# Main.net
KiCad netlist of a schematic drawn in EAGLE
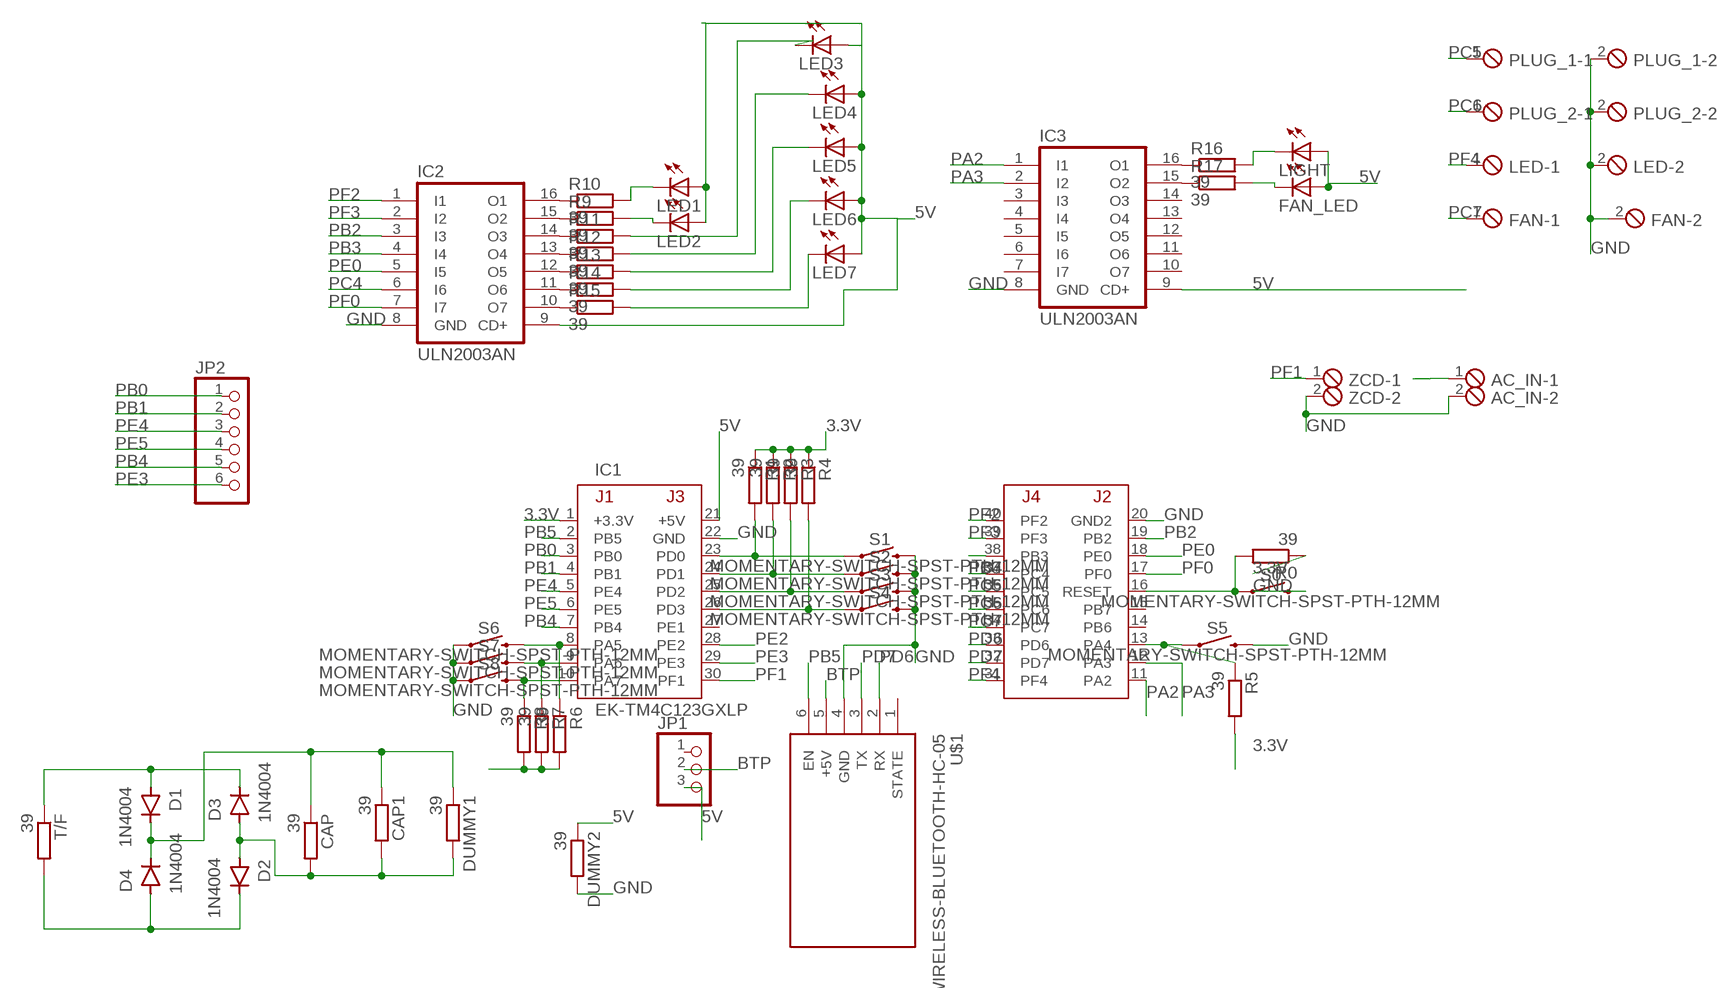
[diagram p0: schematic, sheet 1]

(export (version "E")
  (design (tool "Eeschema 10.0.6"))
  (components
    (comp (ref "AC_IN")
      (value "MPT2")
      (footprint "eagle-import:2POL254")
      (libsource (lib "eagle-import") (part "MPT2"))
    )
    (comp (ref "CAP")
      (value "39")
      (footprint "eagle-import:0204_7")
      (libsource (lib "eagle-import") (part "R0204/7"))
    )
    (comp (ref "CAP1")
      (value "39")
      (footprint "eagle-import:0204_7")
      (libsource (lib "eagle-import") (part "R0204/7"))
    )
    (comp (ref "D1")
      (value "1N4004")
      (footprint "eagle-import:DO-41")
      (fields
        (field (name "DIGIKEY_PART_NUMBER") "1N4004MSCT-ND")
        (field (name "MANUFACTURER") "Micro Commercial Co")
        (field (name "CREATED_BY") "PCBLayout.com")
      )
      (libsource (lib "eagle-import") (part "1N4004"))
    )
    (comp (ref "D2")
      (value "1N4004")
      (footprint "eagle-import:DO-41")
      (fields
        (field (name "DIGIKEY_PART_NUMBER") "1N4004MSCT-ND")
        (field (name "MANUFACTURER") "Micro Commercial Co")
        (field (name "CREATED_BY") "PCBLayout.com")
      )
      (libsource (lib "eagle-import") (part "1N4004"))
    )
    (comp (ref "D3")
      (value "1N4004")
      (footprint "eagle-import:DO-41")
      (fields
        (field (name "DIGIKEY_PART_NUMBER") "1N4004MSCT-ND")
        (field (name "MANUFACTURER") "Micro Commercial Co")
        (field (name "CREATED_BY") "PCBLayout.com")
      )
      (libsource (lib "eagle-import") (part "1N4004"))
    )
    (comp (ref "D4")
      (value "1N4004")
      (footprint "eagle-import:DO-41")
      (fields
        (field (name "DIGIKEY_PART_NUMBER") "1N4004MSCT-ND")
        (field (name "MANUFACTURER") "Micro Commercial Co")
        (field (name "CREATED_BY") "PCBLayout.com")
      )
      (libsource (lib "eagle-import") (part "1N4004"))
    )
    (comp (ref "DUMMY1")
      (value "39")
      (footprint "eagle-import:0204_7")
      (libsource (lib "eagle-import") (part "R0204/7"))
    )
    (comp (ref "DUMMY2")
      (value "39")
      (footprint "eagle-import:0204_7")
      (libsource (lib "eagle-import") (part "R0204/7"))
    )
    (comp (ref "FAN")
      (value "MPT2")
      (footprint "eagle-import:2POL254")
      (libsource (lib "eagle-import") (part "MPT2"))
    )
    (comp (ref "FAN_LED")
      (value "LED3MM")
      (footprint "eagle-import:LED3MM")
      (libsource (lib "eagle-import") (part "LED3MM"))
    )
    (comp (ref "IC1")
      (value "EK-TM4C123GXLP")
      (footprint "eagle-import:TM4C123LAUNCHPAD")
      (fields (field (name "MF") "Texas Instruments") (field (name "MP") "EK-TM4C123GXL"))
      (libsource (lib "eagle-import") (part "EK-TM4C123GXLP"))
    )
    (comp (ref "IC2")
      (value "ULN2003AN")
      (footprint "eagle-import:DIL16")
      (libsource (lib "eagle-import") (part "ULN2003AN"))
    )
    (comp (ref "IC3")
      (value "ULN2003AN")
      (footprint "eagle-import:DIL16")
      (libsource (lib "eagle-import") (part "ULN2003AN"))
    )
    (comp (ref "JP1")
      (value "PINHD-1X3CB")
      (footprint "eagle-import:1X03-CLEANBIG")
      (libsource (lib "eagle-import") (part "PINHD-1X3CB"))
    )
    (comp (ref "JP2")
      (value "PINHD-1X6")
      (footprint "eagle-import:1X06")
      (libsource (lib "eagle-import") (part "PINHD-1X6"))
    )
    (comp (ref "LED")
      (value "MPT2")
      (footprint "eagle-import:2POL254")
      (libsource (lib "eagle-import") (part "MPT2"))
    )
    (comp (ref "LED1")
      (value "LED3MM")
      (footprint "eagle-import:LED3MM")
      (libsource (lib "eagle-import") (part "LED3MM"))
    )
    (comp (ref "LED2")
      (value "LED3MM")
      (footprint "eagle-import:LED3MM")
      (libsource (lib "eagle-import") (part "LED3MM"))
    )
    (comp (ref "LED3")
      (value "LED3MM")
      (footprint "eagle-import:LED3MM")
      (libsource (lib "eagle-import") (part "LED3MM"))
    )
    (comp (ref "LED4")
      (value "LED3MM")
      (footprint "eagle-import:LED3MM")
      (libsource (lib "eagle-import") (part "LED3MM"))
    )
    (comp (ref "LED5")
      (value "LED3MM")
      (footprint "eagle-import:LED3MM")
      (libsource (lib "eagle-import") (part "LED3MM"))
    )
    (comp (ref "LED6")
      (value "LED3MM")
      (footprint "eagle-import:LED3MM")
      (libsource (lib "eagle-import") (part "LED3MM"))
    )
    (comp (ref "LED7")
      (value "LED3MM")
      (footprint "eagle-import:LED3MM")
      (libsource (lib "eagle-import") (part "LED3MM"))
    )
    (comp (ref "LIGHT")
      (value "LED3MM")
      (footprint "eagle-import:LED3MM")
      (libsource (lib "eagle-import") (part "LED3MM"))
    )
    (comp (ref "PLUG_1")
      (value "MPT2")
      (footprint "eagle-import:2POL254")
      (libsource (lib "eagle-import") (part "MPT2"))
    )
    (comp (ref "PLUG_2")
      (value "MPT2")
      (footprint "eagle-import:2POL254")
      (libsource (lib "eagle-import") (part "MPT2"))
    )
    (comp (ref "R0")
      (value "39")
      (footprint "eagle-import:0204_7")
      (libsource (lib "eagle-import") (part "R0204/7"))
    )
    (comp (ref "R1")
      (value "39")
      (footprint "eagle-import:0204_7")
      (libsource (lib "eagle-import") (part "R0204/7"))
    )
    (comp (ref "R2")
      (value "39")
      (footprint "eagle-import:0204_7")
      (libsource (lib "eagle-import") (part "R0204/7"))
    )
    (comp (ref "R3")
      (value "39")
      (footprint "eagle-import:0204_7")
      (libsource (lib "eagle-import") (part "R0204/7"))
    )
    (comp (ref "R4")
      (value "39")
      (footprint "eagle-import:0204_7")
      (libsource (lib "eagle-import") (part "R0204/7"))
    )
    (comp (ref "R5")
      (value "39")
      (footprint "eagle-import:0204_7")
      (libsource (lib "eagle-import") (part "R0204/7"))
    )
    (comp (ref "R6")
      (value "39")
      (footprint "eagle-import:0204_7")
      (libsource (lib "eagle-import") (part "R0204/7"))
    )
    (comp (ref "R7")
      (value "39")
      (footprint "eagle-import:0204_7")
      (libsource (lib "eagle-import") (part "R0204/7"))
    )
    (comp (ref "R8")
      (value "39")
      (footprint "eagle-import:0204_7")
      (libsource (lib "eagle-import") (part "R0204/7"))
    )
    (comp (ref "R9")
      (value "39")
      (footprint "eagle-import:0204_7")
      (libsource (lib "eagle-import") (part "R0204/7"))
    )
    (comp (ref "R10")
      (value "39")
      (footprint "eagle-import:0204_7")
      (libsource (lib "eagle-import") (part "R0204/7"))
    )
    (comp (ref "R11")
      (value "39")
      (footprint "eagle-import:0204_7")
      (libsource (lib "eagle-import") (part "R0204/7"))
    )
    (comp (ref "R12")
      (value "39")
      (footprint "eagle-import:0204_7")
      (libsource (lib "eagle-import") (part "R0204/7"))
    )
    (comp (ref "R13")
      (value "39")
      (footprint "eagle-import:0204_7")
      (libsource (lib "eagle-import") (part "R0204/7"))
    )
    (comp (ref "R14")
      (value "39")
      (footprint "eagle-import:0204_7")
      (libsource (lib "eagle-import") (part "R0204/7"))
    )
    (comp (ref "R15")
      (value "39")
      (footprint "eagle-import:0204_7")
      (libsource (lib "eagle-import") (part "R0204/7"))
    )
    (comp (ref "R16")
      (value "39")
      (footprint "eagle-import:0204_7")
      (libsource (lib "eagle-import") (part "R0204/7"))
    )
    (comp (ref "R17")
      (value "39")
      (footprint "eagle-import:0204_7")
      (libsource (lib "eagle-import") (part "R0204/7"))
    )
    (comp (ref "S0")
      (value "MOMENTARY-SWITCH-SPST-PTH-12MM")
      (footprint "eagle-import:TACTILE_SWITCH_PTH_12MM")
      (libsource (lib "eagle-import") (part "MOMENTARY-SWITCH-SPST-PTH-12MM"))
    )
    (comp (ref "S1")
      (value "MOMENTARY-SWITCH-SPST-PTH-12MM")
      (footprint "eagle-import:TACTILE_SWITCH_PTH_12MM")
      (libsource (lib "eagle-import") (part "MOMENTARY-SWITCH-SPST-PTH-12MM"))
    )
    (comp (ref "S2")
      (value "MOMENTARY-SWITCH-SPST-PTH-12MM")
      (footprint "eagle-import:TACTILE_SWITCH_PTH_12MM")
      (libsource (lib "eagle-import") (part "MOMENTARY-SWITCH-SPST-PTH-12MM"))
    )
    (comp (ref "S3")
      (value "MOMENTARY-SWITCH-SPST-PTH-12MM")
      (footprint "eagle-import:TACTILE_SWITCH_PTH_12MM")
      (libsource (lib "eagle-import") (part "MOMENTARY-SWITCH-SPST-PTH-12MM"))
    )
    (comp (ref "S4")
      (value "MOMENTARY-SWITCH-SPST-PTH-12MM")
      (footprint "eagle-import:TACTILE_SWITCH_PTH_12MM")
      (libsource (lib "eagle-import") (part "MOMENTARY-SWITCH-SPST-PTH-12MM"))
    )
    (comp (ref "S5")
      (value "MOMENTARY-SWITCH-SPST-PTH-12MM")
      (footprint "eagle-import:TACTILE_SWITCH_PTH_12MM")
      (libsource (lib "eagle-import") (part "MOMENTARY-SWITCH-SPST-PTH-12MM"))
    )
    (comp (ref "S6")
      (value "MOMENTARY-SWITCH-SPST-PTH-12MM")
      (footprint "eagle-import:TACTILE_SWITCH_PTH_12MM")
      (libsource (lib "eagle-import") (part "MOMENTARY-SWITCH-SPST-PTH-12MM"))
    )
    (comp (ref "S7")
      (value "MOMENTARY-SWITCH-SPST-PTH-12MM")
      (footprint "eagle-import:TACTILE_SWITCH_PTH_12MM")
      (libsource (lib "eagle-import") (part "MOMENTARY-SWITCH-SPST-PTH-12MM"))
    )
    (comp (ref "S8")
      (value "MOMENTARY-SWITCH-SPST-PTH-12MM")
      (footprint "eagle-import:TACTILE_SWITCH_PTH_12MM")
      (libsource (lib "eagle-import") (part "MOMENTARY-SWITCH-SPST-PTH-12MM"))
    )
    (comp (ref "T/F")
      (value "39")
      (footprint "eagle-import:0204_7")
      (libsource (lib "eagle-import") (part "R0204/7"))
    )
    (comp (ref "U$1")
      (value "WIRELESS-BLUETOOTH-HC-05")
      (footprint "eagle-import:WIRELESS-BLUETOOTH-HC-05")
      (libsource (lib "eagle-import") (part "WIRELESS-BLUETOOTH-HC-05"))
    )
    (comp (ref "ZCD")
      (value "MPT2")
      (footprint "eagle-import:2POL254")
      (libsource (lib "eagle-import") (part "MPT2"))
    )
  )
  (nets
    (net (code "1") (name "/3.3V") (class "Default")
      (node (ref "IC1") (pin "1") (pinfunction "+3.3V_1") (pintype "power_in"))
      (node (ref "R0") (pin "1") (pinfunction "1_1") (pintype "passive"))
      (node (ref "R1") (pin "1") (pinfunction "1_1") (pintype "passive"))
      (node (ref "R2") (pin "1") (pinfunction "1_1") (pintype "passive"))
      (node (ref "R3") (pin "1") (pinfunction "1_1") (pintype "passive"))
      (node (ref "R4") (pin "1") (pinfunction "1_1") (pintype "passive"))
      (node (ref "R5") (pin "2") (pinfunction "2_2") (pintype "passive"))
      (node (ref "R6") (pin "2") (pinfunction "2_2") (pintype "passive"))
      (node (ref "R7") (pin "2") (pinfunction "2_2") (pintype "passive"))
      (node (ref "R8") (pin "2") (pinfunction "2_2") (pintype "passive"))
    )
    (net (code "2") (name "/5V") (class "Default")
      (node (ref "DUMMY2") (pin "1") (pinfunction "1_1") (pintype "passive"))
      (node (ref "FAN_LED") (pin "A") (pinfunction "A_A") (pintype "passive"))
      (node (ref "IC1") (pin "21") (pinfunction "+5V_21") (pintype "power_in"))
      (node (ref "IC2") (pin "9") (pinfunction "CD+_9") (pintype "passive"))
      (node (ref "IC3") (pin "9") (pinfunction "CD+_9") (pintype "passive"))
      (node (ref "JP1") (pin "3") (pinfunction "3_3") (pintype "passive"))
      (node (ref "LED1") (pin "A") (pinfunction "A_A") (pintype "passive"))
      (node (ref "LED2") (pin "A") (pinfunction "A_A") (pintype "passive"))
      (node (ref "LED3") (pin "A") (pinfunction "A_A") (pintype "passive"))
      (node (ref "LED4") (pin "A") (pinfunction "A_A") (pintype "passive"))
      (node (ref "LED5") (pin "A") (pinfunction "A_A") (pintype "passive"))
      (node (ref "LED6") (pin "A") (pinfunction "A_A") (pintype "passive"))
      (node (ref "LED7") (pin "A") (pinfunction "A_A") (pintype "passive"))
      (node (ref "LIGHT") (pin "A") (pinfunction "A_A") (pintype "passive"))
    )
    (net (code "3") (name "/BTP") (class "Default")
      (node (ref "JP1") (pin "2") (pinfunction "2_2") (pintype "passive"))
      (node (ref "U$1") (pin "5") (pinfunction "+5V_5") (pintype "power_in"))
    )
    (net (code "4") (name "/GND") (class "Default")
      (node (ref "AC_IN") (pin "2") (pinfunction "1_2") (pintype "passive"))
      (node (ref "DUMMY2") (pin "2") (pinfunction "2_2") (pintype "passive"))
      (node (ref "FAN") (pin "2") (pinfunction "1_2") (pintype "passive"))
      (node (ref "IC1") (pin "20") (pinfunction "GND2_20") (pintype "power_in"))
      (node (ref "IC1") (pin "22") (pinfunction "GND_22") (pintype "power_in"))
      (node (ref "IC2") (pin "8") (pinfunction "GND_8") (pintype "power_in"))
      (node (ref "IC3") (pin "8") (pinfunction "GND_8") (pintype "power_in"))
      (node (ref "LED") (pin "2") (pinfunction "1_2") (pintype "passive"))
      (node (ref "PLUG_1") (pin "2") (pinfunction "1_2") (pintype "passive"))
      (node (ref "PLUG_2") (pin "2") (pinfunction "1_2") (pintype "passive"))
      (node (ref "S0") (pin "3") (pinfunction "2_3") (pintype "passive"))
      (node (ref "S1") (pin "3") (pinfunction "2_3") (pintype "passive"))
      (node (ref "S2") (pin "3") (pinfunction "2_3") (pintype "passive"))
      (node (ref "S3") (pin "3") (pinfunction "2_3") (pintype "passive"))
      (node (ref "S4") (pin "3") (pinfunction "2_3") (pintype "passive"))
      (node (ref "S5") (pin "3") (pinfunction "2_3") (pintype "passive"))
      (node (ref "S6") (pin "1") (pinfunction "1_1") (pintype "passive"))
      (node (ref "S7") (pin "1") (pinfunction "1_1") (pintype "passive"))
      (node (ref "S8") (pin "1") (pinfunction "1_1") (pintype "passive"))
      (node (ref "U$1") (pin "4") (pinfunction "GND_4") (pintype "power_in"))
      (node (ref "ZCD") (pin "2") (pinfunction "1_2") (pintype "passive"))
    )
    (net (code "5") (name "/PA2") (class "Default")
      (node (ref "IC1") (pin "11") (pinfunction "PA2_11") (pintype "bidirectional"))
      (node (ref "IC3") (pin "1") (pinfunction "I1_1") (pintype "input"))
    )
    (net (code "6") (name "/PA3") (class "Default")
      (node (ref "IC1") (pin "12") (pinfunction "PA3_12") (pintype "bidirectional"))
      (node (ref "IC3") (pin "2") (pinfunction "I2_2") (pintype "input"))
    )
    (net (code "7") (name "/PB0") (class "Default")
      (node (ref "IC1") (pin "3") (pinfunction "PB0_3") (pintype "bidirectional"))
      (node (ref "JP2") (pin "1") (pinfunction "1_1") (pintype "passive"))
    )
    (net (code "8") (name "/PB1") (class "Default")
      (node (ref "IC1") (pin "4") (pinfunction "PB1_4") (pintype "bidirectional"))
      (node (ref "JP2") (pin "2") (pinfunction "2_2") (pintype "passive"))
    )
    (net (code "9") (name "/PB2") (class "Default")
      (node (ref "IC1") (pin "19") (pinfunction "PB2_19") (pintype "bidirectional"))
      (node (ref "IC2") (pin "3") (pinfunction "I3_3") (pintype "input"))
    )
    (net (code "10") (name "/PB3") (class "Default")
      (node (ref "IC1") (pin "38") (pinfunction "PB3_38") (pintype "bidirectional"))
      (node (ref "IC2") (pin "4") (pinfunction "I4_4") (pintype "input"))
    )
    (net (code "11") (name "/PB4") (class "Default")
      (node (ref "IC1") (pin "7") (pinfunction "PB4_7") (pintype "bidirectional"))
      (node (ref "JP2") (pin "5") (pinfunction "5_5") (pintype "passive"))
    )
    (net (code "12") (name "/PB5") (class "Default")
      (node (ref "IC1") (pin "2") (pinfunction "PB5_2") (pintype "bidirectional"))
      (node (ref "U$1") (pin "6") (pinfunction "EN_6") (pintype "bidirectional"))
    )
    (net (code "13") (name "/PC4") (class "Default")
      (node (ref "IC1") (pin "37") (pinfunction "PC4_37") (pintype "bidirectional"))
      (node (ref "IC2") (pin "6") (pinfunction "I6_6") (pintype "input"))
    )
    (net (code "14") (name "/PC5") (class "Default")
      (node (ref "IC1") (pin "36") (pinfunction "PC5_36") (pintype "bidirectional"))
      (node (ref "PLUG_1") (pin "1") (pinfunction "1_1") (pintype "passive"))
    )
    (net (code "15") (name "/PC6") (class "Default")
      (node (ref "IC1") (pin "35") (pinfunction "PC6_35") (pintype "bidirectional"))
      (node (ref "PLUG_2") (pin "1") (pinfunction "1_1") (pintype "passive"))
    )
    (net (code "16") (name "/PC7") (class "Default")
      (node (ref "FAN") (pin "1") (pinfunction "1_1") (pintype "passive"))
      (node (ref "IC1") (pin "34") (pinfunction "PC7_34") (pintype "bidirectional"))
    )
    (net (code "17") (name "/PD6") (class "Default")
      (node (ref "IC1") (pin "33") (pinfunction "PD6_33") (pintype "bidirectional"))
      (node (ref "U$1") (pin "2") (pinfunction "RX_2") (pintype "bidirectional"))
    )
    (net (code "18") (name "/PD7") (class "Default")
      (node (ref "IC1") (pin "32") (pinfunction "PD7_32") (pintype "bidirectional"))
      (node (ref "U$1") (pin "3") (pinfunction "TX_3") (pintype "bidirectional"))
    )
    (net (code "19") (name "/PE0") (class "Default")
      (node (ref "IC1") (pin "18") (pinfunction "PE0_18") (pintype "bidirectional"))
      (node (ref "IC2") (pin "5") (pinfunction "I5_5") (pintype "input"))
    )
    (net (code "20") (name "/PE2") (class "Default")
      (node (ref "AC_IN") (pin "1") (pinfunction "1_1") (pintype "passive"))
      (node (ref "IC1") (pin "28") (pinfunction "PE2_28") (pintype "bidirectional"))
    )
    (net (code "21") (name "/PE3") (class "Default")
      (node (ref "IC1") (pin "29") (pinfunction "PE3_29") (pintype "bidirectional"))
      (node (ref "JP2") (pin "6") (pinfunction "6_6") (pintype "passive"))
    )
    (net (code "22") (name "/PE4") (class "Default")
      (node (ref "IC1") (pin "5") (pinfunction "PE4_5") (pintype "bidirectional"))
      (node (ref "JP2") (pin "3") (pinfunction "3_3") (pintype "passive"))
    )
    (net (code "23") (name "/PE5") (class "Default")
      (node (ref "IC1") (pin "6") (pinfunction "PE5_6") (pintype "bidirectional"))
      (node (ref "JP2") (pin "4") (pinfunction "4_4") (pintype "passive"))
    )
    (net (code "24") (name "/PF0") (class "Default")
      (node (ref "IC1") (pin "17") (pinfunction "PF0_17") (pintype "bidirectional"))
      (node (ref "IC2") (pin "7") (pinfunction "I7_7") (pintype "input"))
    )
    (net (code "25") (name "/PF1") (class "Default")
      (node (ref "IC1") (pin "30") (pinfunction "PF1_30") (pintype "bidirectional"))
      (node (ref "ZCD") (pin "1") (pinfunction "1_1") (pintype "passive"))
    )
    (net (code "26") (name "/PF2") (class "Default")
      (node (ref "IC1") (pin "40") (pinfunction "PF2_40") (pintype "bidirectional"))
      (node (ref "IC2") (pin "1") (pinfunction "I1_1") (pintype "input"))
    )
    (net (code "27") (name "/PF3") (class "Default")
      (node (ref "IC1") (pin "39") (pinfunction "PF3_39") (pintype "bidirectional"))
      (node (ref "IC2") (pin "2") (pinfunction "I2_2") (pintype "input"))
    )
    (net (code "28") (name "/PF4") (class "Default")
      (node (ref "IC1") (pin "31") (pinfunction "PF4_31") (pintype "bidirectional"))
      (node (ref "LED") (pin "1") (pinfunction "1_1") (pintype "passive"))
    )
    (net (code "29") (name "Net-(CAP-Pad1)") (class "Default")
      (node (ref "CAP") (pin "1") (pinfunction "1_1") (pintype "passive"))
      (node (ref "CAP1") (pin "1") (pinfunction "1_1") (pintype "passive"))
      (node (ref "D1") (pin "C") (pinfunction "C_C") (pintype "passive"))
      (node (ref "D4") (pin "C") (pinfunction "C_C") (pintype "passive"))
      (node (ref "DUMMY1") (pin "1") (pinfunction "1_1") (pintype "passive"))
    )
    (net (code "30") (name "Net-(CAP-Pad2)") (class "Default")
      (node (ref "CAP") (pin "2") (pinfunction "2_2") (pintype "passive"))
      (node (ref "CAP1") (pin "2") (pinfunction "2_2") (pintype "passive"))
      (node (ref "D2") (pin "A") (pinfunction "A_A") (pintype "passive"))
      (node (ref "D3") (pin "A") (pinfunction "A_A") (pintype "passive"))
      (node (ref "DUMMY1") (pin "2") (pinfunction "2_2") (pintype "passive"))
    )
    (net (code "31") (name "Net-(D1-PadA)") (class "Default")
      (node (ref "D1") (pin "A") (pinfunction "A_A") (pintype "passive"))
      (node (ref "D3") (pin "C") (pinfunction "C_C") (pintype "passive"))
      (node (ref "T/F") (pin "1") (pinfunction "1_1") (pintype "passive"))
    )
    (net (code "32") (name "Net-(D2-PadC)") (class "Default")
      (node (ref "D2") (pin "C") (pinfunction "C_C") (pintype "passive"))
      (node (ref "D4") (pin "A") (pinfunction "A_A") (pintype "passive"))
      (node (ref "T/F") (pin "2") (pinfunction "2_2") (pintype "passive"))
    )
    (net (code "33") (name "Net-(FAN_LED-C)") (class "Default")
      (node (ref "FAN_LED") (pin "K") (pinfunction "C_K") (pintype "passive"))
      (node (ref "R17") (pin "2") (pinfunction "2_2") (pintype "passive"))
    )
    (net (code "34") (name "Net-(IC1-PA4)") (class "Default")
      (node (ref "IC1") (pin "13") (pinfunction "PA4_13") (pintype "bidirectional"))
      (node (ref "R5") (pin "1") (pinfunction "1_1") (pintype "passive"))
      (node (ref "S5") (pin "1") (pinfunction "1_1") (pintype "passive"))
    )
    (net (code "35") (name "Net-(IC1-PA5)") (class "Default")
      (node (ref "IC1") (pin "8") (pinfunction "PA5_8") (pintype "bidirectional"))
      (node (ref "R6") (pin "1") (pinfunction "1_1") (pintype "passive"))
      (node (ref "S6") (pin "3") (pinfunction "2_3") (pintype "passive"))
    )
    (net (code "36") (name "Net-(IC1-PA6)") (class "Default")
      (node (ref "IC1") (pin "9") (pinfunction "PA6_9") (pintype "bidirectional"))
      (node (ref "R7") (pin "1") (pinfunction "1_1") (pintype "passive"))
      (node (ref "S7") (pin "3") (pinfunction "2_3") (pintype "passive"))
    )
    (net (code "37") (name "Net-(IC1-PA7)") (class "Default")
      (node (ref "IC1") (pin "10") (pinfunction "PA7_10") (pintype "bidirectional"))
      (node (ref "R8") (pin "1") (pinfunction "1_1") (pintype "passive"))
      (node (ref "S8") (pin "3") (pinfunction "2_3") (pintype "passive"))
    )
    (net (code "38") (name "Net-(IC1-PD0)") (class "Default")
      (node (ref "IC1") (pin "23") (pinfunction "PD0_23") (pintype "bidirectional"))
      (node (ref "R1") (pin "2") (pinfunction "2_2") (pintype "passive"))
      (node (ref "S1") (pin "1") (pinfunction "1_1") (pintype "passive"))
    )
    (net (code "39") (name "Net-(IC1-PD1)") (class "Default")
      (node (ref "IC1") (pin "24") (pinfunction "PD1_24") (pintype "bidirectional"))
      (node (ref "R2") (pin "2") (pinfunction "2_2") (pintype "passive"))
      (node (ref "S2") (pin "1") (pinfunction "1_1") (pintype "passive"))
    )
    (net (code "40") (name "Net-(IC1-PD2)") (class "Default")
      (node (ref "IC1") (pin "25") (pinfunction "PD2_25") (pintype "bidirectional"))
      (node (ref "R3") (pin "2") (pinfunction "2_2") (pintype "passive"))
      (node (ref "S3") (pin "1") (pinfunction "1_1") (pintype "passive"))
    )
    (net (code "41") (name "Net-(IC1-PD3)") (class "Default")
      (node (ref "IC1") (pin "26") (pinfunction "PD3_26") (pintype "bidirectional"))
      (node (ref "R4") (pin "2") (pinfunction "2_2") (pintype "passive"))
      (node (ref "S4") (pin "1") (pinfunction "1_1") (pintype "passive"))
    )
    (net (code "42") (name "Net-(IC1-RESET)") (class "Default")
      (node (ref "IC1") (pin "16") (pinfunction "RESET_16") (pintype "input"))
      (node (ref "R0") (pin "2") (pinfunction "2_2") (pintype "passive"))
      (node (ref "S0") (pin "1") (pinfunction "1_1") (pintype "passive"))
    )
    (net (code "43") (name "Net-(IC2-O1)") (class "Default")
      (node (ref "IC2") (pin "16") (pinfunction "O1_16") (pintype "open_collector"))
      (node (ref "R10") (pin "1") (pinfunction "1_1") (pintype "passive"))
    )
    (net (code "44") (name "Net-(IC2-O2)") (class "Default")
      (node (ref "IC2") (pin "15") (pinfunction "O2_15") (pintype "open_collector"))
      (node (ref "R9") (pin "1") (pinfunction "1_1") (pintype "passive"))
    )
    (net (code "45") (name "Net-(IC2-O3)") (class "Default")
      (node (ref "IC2") (pin "14") (pinfunction "O3_14") (pintype "open_collector"))
      (node (ref "R11") (pin "1") (pinfunction "1_1") (pintype "passive"))
    )
    (net (code "46") (name "Net-(IC2-O4)") (class "Default")
      (node (ref "IC2") (pin "13") (pinfunction "O4_13") (pintype "open_collector"))
      (node (ref "R12") (pin "1") (pinfunction "1_1") (pintype "passive"))
    )
    (net (code "47") (name "Net-(IC2-O5)") (class "Default")
      (node (ref "IC2") (pin "12") (pinfunction "O5_12") (pintype "open_collector"))
      (node (ref "R13") (pin "1") (pinfunction "1_1") (pintype "passive"))
    )
    (net (code "48") (name "Net-(IC2-O6)") (class "Default")
      (node (ref "IC2") (pin "11") (pinfunction "O6_11") (pintype "open_collector"))
      (node (ref "R14") (pin "1") (pinfunction "1_1") (pintype "passive"))
    )
    (net (code "49") (name "Net-(IC2-O7)") (class "Default")
      (node (ref "IC2") (pin "10") (pinfunction "O7_10") (pintype "open_collector"))
      (node (ref "R15") (pin "1") (pinfunction "1_1") (pintype "passive"))
    )
    (net (code "50") (name "Net-(IC3-O1)") (class "Default")
      (node (ref "IC3") (pin "16") (pinfunction "O1_16") (pintype "open_collector"))
      (node (ref "R16") (pin "1") (pinfunction "1_1") (pintype "passive"))
    )
    (net (code "51") (name "Net-(IC3-O2)") (class "Default")
      (node (ref "IC3") (pin "15") (pinfunction "O2_15") (pintype "open_collector"))
      (node (ref "R17") (pin "1") (pinfunction "1_1") (pintype "passive"))
    )
    (net (code "52") (name "Net-(LED1-C)") (class "Default")
      (node (ref "LED1") (pin "K") (pinfunction "C_K") (pintype "passive"))
      (node (ref "R10") (pin "2") (pinfunction "2_2") (pintype "passive"))
    )
    (net (code "53") (name "Net-(LED2-C)") (class "Default")
      (node (ref "LED2") (pin "K") (pinfunction "C_K") (pintype "passive"))
      (node (ref "R9") (pin "2") (pinfunction "2_2") (pintype "passive"))
    )
    (net (code "54") (name "Net-(LED3-C)") (class "Default")
      (node (ref "LED3") (pin "K") (pinfunction "C_K") (pintype "passive"))
      (node (ref "R11") (pin "2") (pinfunction "2_2") (pintype "passive"))
    )
    (net (code "55") (name "Net-(LED4-C)") (class "Default")
      (node (ref "LED4") (pin "K") (pinfunction "C_K") (pintype "passive"))
      (node (ref "R12") (pin "2") (pinfunction "2_2") (pintype "passive"))
    )
    (net (code "56") (name "Net-(LED5-C)") (class "Default")
      (node (ref "LED5") (pin "K") (pinfunction "C_K") (pintype "passive"))
      (node (ref "R13") (pin "2") (pinfunction "2_2") (pintype "passive"))
    )
    (net (code "57") (name "Net-(LED6-C)") (class "Default")
      (node (ref "LED6") (pin "K") (pinfunction "C_K") (pintype "passive"))
      (node (ref "R14") (pin "2") (pinfunction "2_2") (pintype "passive"))
    )
    (net (code "58") (name "Net-(LED7-C)") (class "Default")
      (node (ref "LED7") (pin "K") (pinfunction "C_K") (pintype "passive"))
      (node (ref "R15") (pin "2") (pinfunction "2_2") (pintype "passive"))
    )
    (net (code "59") (name "Net-(LIGHT-C)") (class "Default")
      (node (ref "LIGHT") (pin "K") (pinfunction "C_K") (pintype "passive"))
      (node (ref "R16") (pin "2") (pinfunction "2_2") (pintype "passive"))
    )
    (net (code "60") (name "unconnected-(IC1-PB6-Pad14)") (class "Default")
      (node (ref "IC1") (pin "14") (pinfunction "PB6_14") (pintype "bidirectional"))
    )
    (net (code "61") (name "unconnected-(IC1-PB7-Pad15)") (class "Default")
      (node (ref "IC1") (pin "15") (pinfunction "PB7_15") (pintype "bidirectional"))
    )
    (net (code "62") (name "unconnected-(IC1-PE1-Pad27)") (class "Default")
      (node (ref "IC1") (pin "27") (pinfunction "PE1_27") (pintype "bidirectional"))
    )
    (net (code "63") (name "unconnected-(IC3-I3-Pad3)") (class "Default")
      (node (ref "IC3") (pin "3") (pinfunction "I3_3") (pintype "input"))
    )
    (net (code "64") (name "unconnected-(IC3-I4-Pad4)") (class "Default")
      (node (ref "IC3") (pin "4") (pinfunction "I4_4") (pintype "input"))
    )
    (net (code "65") (name "unconnected-(IC3-I5-Pad5)") (class "Default")
      (node (ref "IC3") (pin "5") (pinfunction "I5_5") (pintype "input"))
    )
    (net (code "66") (name "unconnected-(IC3-I6-Pad6)") (class "Default")
      (node (ref "IC3") (pin "6") (pinfunction "I6_6") (pintype "input"))
    )
    (net (code "67") (name "unconnected-(IC3-I7-Pad7)") (class "Default")
      (node (ref "IC3") (pin "7") (pinfunction "I7_7") (pintype "input"))
    )
    (net (code "68") (name "unconnected-(IC3-O3-Pad14)") (class "Default")
      (node (ref "IC3") (pin "14") (pinfunction "O3_14") (pintype "open_collector"))
    )
    (net (code "69") (name "unconnected-(IC3-O4-Pad13)") (class "Default")
      (node (ref "IC3") (pin "13") (pinfunction "O4_13") (pintype "open_collector"))
    )
    (net (code "70") (name "unconnected-(IC3-O5-Pad12)") (class "Default")
      (node (ref "IC3") (pin "12") (pinfunction "O5_12") (pintype "open_collector"))
    )
    (net (code "71") (name "unconnected-(IC3-O6-Pad11)") (class "Default")
      (node (ref "IC3") (pin "11") (pinfunction "O6_11") (pintype "open_collector"))
    )
    (net (code "72") (name "unconnected-(IC3-O7-Pad10)") (class "Default")
      (node (ref "IC3") (pin "10") (pinfunction "O7_10") (pintype "open_collector"))
    )
    (net (code "73") (name "unconnected-(JP1-Pad1)") (class "Default")
      (node (ref "JP1") (pin "1") (pinfunction "1_1") (pintype "passive"))
    )
    (net (code "74") (name "unconnected-(U$1-STATE-Pad1)") (class "Default")
      (node (ref "U$1") (pin "1") (pinfunction "STATE_1") (pintype "bidirectional"))
    )
  )
)
